# schametic.net
KiCad netlist of a schematic drawn in Altium Designer
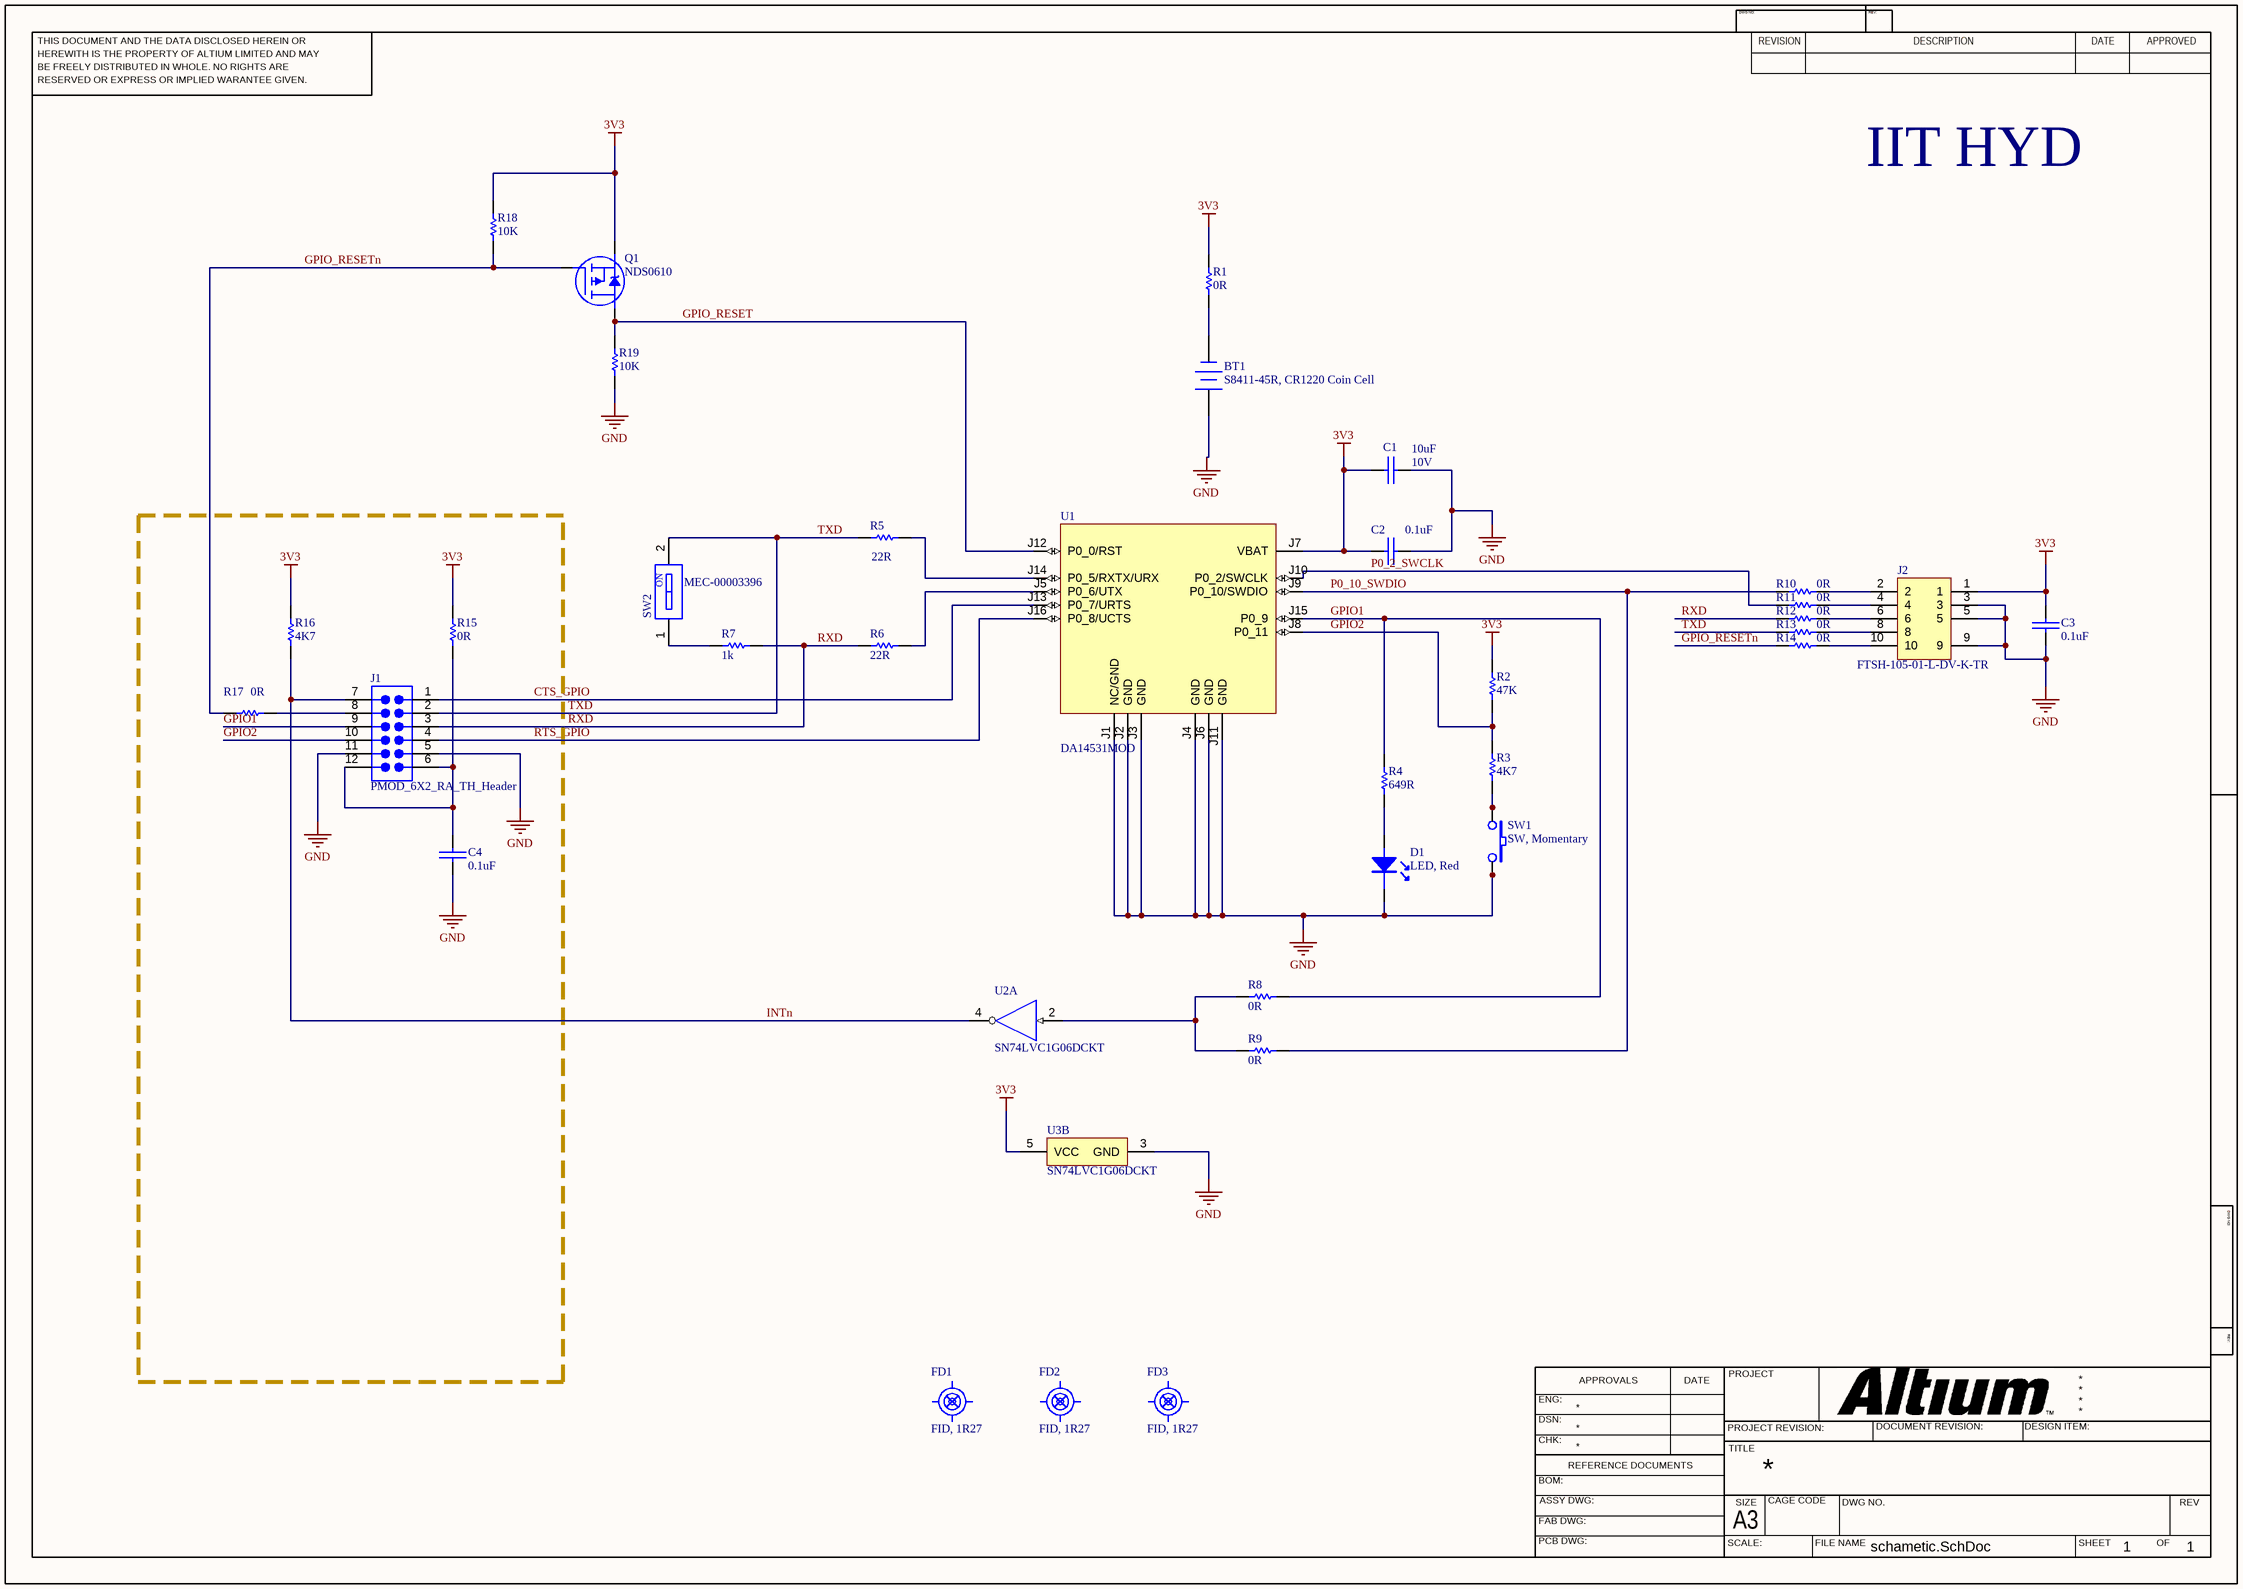
[diagram p0: schametic.SchDoc]

(export (version "E")
  (design (tool "Eeschema 10.0.6"))
  (components
    (comp (ref "BT1")
      (value "S8411-45R, CR1220 Coin Cell")
      (footprint "HWN_S8411-45R")
      (description "Battery Holder, 12 mm Coin Cell, CR1220 SM")
      (fields (field (name "MANUFACTURER'S PART #") "S8411-45R") (field (name "MANUFACTURER") "Harwin"))
      (libsource (lib "Low Power Bluetooth PMOD RevA") (part "BT-S8411-45R-SR-HWN"))
    )
    (comp (ref "C1")
      (value "10uF")
      (footprint "CAPC1608X10N")
      (description "Capacitor, 10uF, 10V, SM")
      (fields
        (field (name "MANUFACTURER'S PART #") "GRM188R61A106KE69D")
        (field (name "MANUFACTURER") "Murata")
        (field (name "VOLTAGE RATING") "10V")
      )
      (libsource (lib "Low Power Bluetooth PMOD RevA") (part "CI-10uF-10V-X5R-SR-MRT"))
    )
    (comp (ref "C2")
      (value "0.1uF")
      (footprint "CAPC1608X09N")
      (description "Capacitor, 0.1uF, 50V, SM")
      (fields
        (field (name "MANUFACTURER'S PART #") "CC0603KRX7R9BB104")
        (field (name "MANUFACTURER") "Yageo")
      )
      (libsource (lib "Low Power Bluetooth PMOD RevA") (part "CI-0.1uF-50V-X7R-SR-YAG"))
    )
    (comp (ref "C3")
      (value "0.1uF")
      (footprint "CAPC1608X09N")
      (description "Capacitor, 0.1uF, 50V, SM")
      (fields
        (field (name "MANUFACTURER'S PART #") "CC0603KRX7R9BB104")
        (field (name "MANUFACTURER") "Yageo")
      )
      (libsource (lib "Low Power Bluetooth PMOD RevA") (part "CI-0.1uF-50V-X7R-SR-YAG"))
    )
    (comp (ref "C4")
      (value "0.1uF")
      (footprint "CAPC1608X09N")
      (description "Capacitor, 0.1uF, 50V, SM")
      (fields
        (field (name "MANUFACTURER'S PART #") "CC0603KRX7R9BB104")
        (field (name "MANUFACTURER") "Yageo")
      )
      (libsource (lib "Low Power Bluetooth PMOD RevA") (part "CI-0.1uF-50V-X7R-SR-YAG"))
    )
    (comp (ref "D1")
      (value "LED, Red")
      (footprint "DIOC2012X08N_WTE")
      (description "LED, Red, 0805 SM")
      (fields
        (field (name "MANUFACTURER'S PART #") "150080RS75000")
        (field (name "MANUFACTURER") "Wurth Elektronik")
      )
      (libsource (lib "Low Power Bluetooth PMOD RevA") (part "DA-150080RS75000-SR-WTE"))
    )
    (comp (ref "FD1")
      (value "FID, 1R27")
      (footprint "FD_ML_1R27")
      (description "Fiducial, 1.27mm D, Multilayer")
      (fields (field (name "MANUFACTURER") "PCB Fabricator"))
      (libsource (lib "Low Power Bluetooth PMOD RevA") (part "FD-ML1R27-SR-BDH"))
    )
    (comp (ref "FD2")
      (value "FID, 1R27")
      (footprint "FD_ML_1R27")
      (description "Fiducial, 1.27mm D, Multilayer")
      (fields (field (name "MANUFACTURER") "PCB Fabricator"))
      (libsource (lib "Low Power Bluetooth PMOD RevA") (part "FD-ML1R27-SR-BDH"))
    )
    (comp (ref "FD3")
      (value "FID, 1R27")
      (footprint "FD_ML_1R27")
      (description "Fiducial, 1.27mm D, Multilayer")
      (fields (field (name "MANUFACTURER") "PCB Fabricator"))
      (libsource (lib "Low Power Bluetooth PMOD RevA") (part "FD-ML1R27-SR-BDH"))
    )
    (comp (ref "J1")
      (value "PMOD_6X2_RA_TH_Header")
      (footprint "PMOD-CONN2X6-RA-TH-HDR")
      (description "Male Header 0.1\" pitch PMOD 2x6 Right Angle, through hole")
      (libsource (lib "Low Power Bluetooth PMOD RevA") (part "CMP-024-000000-2"))
    )
    (comp (ref "J2")
      (value "FTSH-105-01-L-DV-K-TR")
      (footprint "SAM_FTSH-105-01-L-DV-007-K")
      (description "Connector, 2X5 Header, Vertical, 1.27mm Pitch, Pin 7, SM")
      (fields
        (field (name "MANUFACTURER'S PART #") "FTSH-105-01-L-DV-007-K")
        (field (name "MANUFACTURER") "Samtec")
      )
      (libsource (lib "Low Power Bluetooth PMOD RevA") (part "JH-2X5VH-FTSH-105-01-L-DV-007-K-SR-SAM"))
    )
    (comp (ref "Q1")
      (value "NDS0610")
      (footprint "SOT95P275X112-3NF")
      (description "Transistor, P-Ch Mosfet, 60V, 120mA, 10Ohm, SM")
      (fields (field (name "MANUFACTURER") "On Semiconductor"))
      (libsource (lib "Low Power Bluetooth PMOD RevA") (part "QA-NDS0610-SR-ONS"))
    )
    (comp (ref "R1")
      (value "0R")
      (footprint "RESC1608X06N")
      (description "Resistor, 0 ohms, 1/8W, 1%, SM")
      (fields (field (name "MANUFACTURER'S PART #") "RK73Z1JTTD") (field (name "MANUFACTURER") "KOA Speer"))
      (libsource (lib "Low Power Bluetooth PMOD RevA") (part "RP-0-SR-KOA"))
    )
    (comp (ref "R2")
      (value "47K")
      (footprint "RESC1608X06N")
      (description "Resistor, 47K ohms, 1/8W, 1%, SM")
      (fields
        (field (name "MANUFACTURER'S PART #") "RK73H1JTTD6802F")
        (field (name "MANUFACTURER") "KOA Speer")
      )
      (libsource (lib "Low Power Bluetooth PMOD RevA") (part "RP-47K-SR-KOA"))
    )
    (comp (ref "R3")
      (value "4K7")
      (footprint "RESC1608X06N")
      (description "Resistor, 4.7K ohms, 1/8W, 1%, SM")
      (fields
        (field (name "MANUFACTURER'S PART #") "RK73H1JTTD4701F")
        (field (name "MANUFACTURER") "KOA Speer")
      )
      (libsource (lib "Low Power Bluetooth PMOD RevA") (part "RP-4.7K-SR-KOA"))
    )
    (comp (ref "R4")
      (value "649R")
      (footprint "RESC1608X06N")
      (description "Resistor, 649 ohms, 1/8W, 1%, SM")
      (fields
        (field (name "MANUFACTURER'S PART #") "RK73H1JTTD6490F")
        (field (name "MANUFACTURER") "KOA Speer")
      )
      (libsource (lib "Low Power Bluetooth PMOD RevA") (part "RP-649-SR-KOA"))
    )
    (comp (ref "R5")
      (value "22R")
      (footprint "RESC1608X06N")
      (description "Resistor, 22 ohms, 1/8W, 1%, SM")
      (fields
        (field (name "MANUFACTURER'S PART #") "RK73H1JTTD22R0F")
        (field (name "MANUFACTURER") "KOA Speer")
      )
      (libsource (lib "Low Power Bluetooth PMOD RevA") (part "RP-22-SR-KOA"))
    )
    (comp (ref "R6")
      (value "22R")
      (footprint "RESC1608X06N")
      (description "Resistor, 22 ohms, 1/8W, 1%, SM")
      (fields
        (field (name "MANUFACTURER'S PART #") "RK73H1JTTD22R0F")
        (field (name "MANUFACTURER") "KOA Speer")
      )
      (libsource (lib "Low Power Bluetooth PMOD RevA") (part "RP-22-SR-KOA"))
    )
    (comp (ref "R7")
      (value "1k")
      (footprint "RESC0603-01")
      (description "Chip Resistor Thick Film 0603 1K0 ohm 1% 1/10W")
      (fields (field (name "TOLERANCE") "1%") (field (name "MFG") "Vishay Dale"))
      (libsource (lib "Low Power Bluetooth PMOD RevA") (part "CMP-009-00240-1"))
    )
    (comp (ref "R8")
      (value "0R")
      (footprint "RESC1608X06N")
      (description "Resistor, 0 ohms, 1/8W, 1%, SM")
      (fields (field (name "MANUFACTURER'S PART #") "RK73Z1JTTD") (field (name "MANUFACTURER") "KOA Speer"))
      (libsource (lib "Low Power Bluetooth PMOD RevA") (part "RP-0-SR-KOA"))
    )
    (comp (ref "R9")
      (value "0R")
      (footprint "RESC1608X06N")
      (description "Resistor, 0 ohms, 1/8W, 1%, SM")
      (fields (field (name "MANUFACTURER'S PART #") "RK73Z1JTTD") (field (name "MANUFACTURER") "KOA Speer"))
      (libsource (lib "Low Power Bluetooth PMOD RevA") (part "RP-0-SR-KOA"))
    )
    (comp (ref "R10")
      (value "0R")
      (footprint "RESC1608X06N")
      (description "Resistor, 0 ohms, 1/8W, 1%, SM")
      (fields (field (name "MANUFACTURER'S PART #") "RK73Z1JTTD") (field (name "MANUFACTURER") "KOA Speer"))
      (libsource (lib "Low Power Bluetooth PMOD RevA") (part "RP-0-SR-KOA"))
    )
    (comp (ref "R11")
      (value "0R")
      (footprint "RESC1608X06N")
      (description "Resistor, 0 ohms, 1/8W, 1%, SM")
      (fields (field (name "MANUFACTURER'S PART #") "RK73Z1JTTD") (field (name "MANUFACTURER") "KOA Speer"))
      (libsource (lib "Low Power Bluetooth PMOD RevA") (part "RP-0-SR-KOA"))
    )
    (comp (ref "R12")
      (value "0R")
      (footprint "RESC1608X06N")
      (description "Resistor, 0 ohms, 1/8W, 1%, SM")
      (fields (field (name "MANUFACTURER'S PART #") "RK73Z1JTTD") (field (name "MANUFACTURER") "KOA Speer"))
      (libsource (lib "Low Power Bluetooth PMOD RevA") (part "RP-0-SR-KOA"))
    )
    (comp (ref "R13")
      (value "0R")
      (footprint "RESC1608X06N")
      (description "Resistor, 0 ohms, 1/8W, 1%, SM")
      (fields (field (name "MANUFACTURER'S PART #") "RK73Z1JTTD") (field (name "MANUFACTURER") "KOA Speer"))
      (libsource (lib "Low Power Bluetooth PMOD RevA") (part "RP-0-SR-KOA"))
    )
    (comp (ref "R14")
      (value "0R")
      (footprint "RESC1608X06N")
      (description "Resistor, 0 ohms, 1/8W, 1%, SM")
      (fields (field (name "MANUFACTURER'S PART #") "RK73Z1JTTD") (field (name "MANUFACTURER") "KOA Speer"))
      (libsource (lib "Low Power Bluetooth PMOD RevA") (part "RP-0-SR-KOA"))
    )
    (comp (ref "R15")
      (value "0R")
      (footprint "RESC1608X06N")
      (description "Resistor, 0 ohms, 1/8W, 1%, SM")
      (fields (field (name "MANUFACTURER'S PART #") "RK73Z1JTTD") (field (name "MANUFACTURER") "KOA Speer"))
      (libsource (lib "Low Power Bluetooth PMOD RevA") (part "RP-0-SR-KOA"))
    )
    (comp (ref "R16")
      (value "4K7")
      (footprint "RESC1608X06N")
      (description "Resistor, 4.7K ohms, 1/8W, 1%, SM")
      (fields
        (field (name "MANUFACTURER'S PART #") "RK73H1JTTD4701F")
        (field (name "MANUFACTURER") "KOA Speer")
      )
      (libsource (lib "Low Power Bluetooth PMOD RevA") (part "RP-4.7K-SR-KOA"))
    )
    (comp (ref "R17")
      (value "0R")
      (footprint "RESC1608X06N")
      (description "Resistor, 0 ohms, 1/8W, 1%, SM")
      (fields (field (name "MANUFACTURER'S PART #") "RK73Z1JTTD") (field (name "MANUFACTURER") "KOA Speer"))
      (libsource (lib "Low Power Bluetooth PMOD RevA") (part "RP-0-SR-KOA"))
    )
    (comp (ref "R18")
      (value "10K")
      (footprint "RESC1608X06N")
      (description "Resistor, 10K ohms, 1/8W, 1%, SM")
      (fields
        (field (name "MANUFACTURER'S PART #") "RK73H1JTTD1002F")
        (field (name "MANUFACTURER") "KOA Speer")
      )
      (libsource (lib "Low Power Bluetooth PMOD RevA") (part "RP-10K-SR-KOA"))
    )
    (comp (ref "R19")
      (value "10K")
      (footprint "RESC1608X06N")
      (description "Resistor, 10K ohms, 1/8W, 1%, SM")
      (fields
        (field (name "MANUFACTURER'S PART #") "RK73H1JTTD1002F")
        (field (name "MANUFACTURER") "KOA Speer")
      )
      (libsource (lib "Low Power Bluetooth PMOD RevA") (part "RP-10K-SR-KOA"))
    )
    (comp (ref "SW1")
      (value "SW, Momentary")
      (footprint "SW_PTS810")
      (description "Switch, Pushbutton, Top Actuated, SM")
      (fields
        (field (name "MANUFACTURER'S PART #") "PTS810 SJG 250 SMTR LFS")
        (field (name "MANUFACTURER") "C&K Components")
      )
      (libsource (lib "Low Power Bluetooth PMOD RevA") (part "SW-PTS810SJG250-SR-CKC"))
    )
    (comp (ref "SW2")
      (value "MEC-00003396")
      (footprint "416131160801")
      (description "WS-DISV Small Compact SMT Flat Actuator with Top Tape 1.27 mm")
      (fields (field (name "VOLTAGE") "50V") (field (name "CHECKED") "OK"))
      (libsource (lib "Low Power Bluetooth PMOD RevA") (part "CMP-011-00036-1"))
    )
    (comp (ref "U1")
      (value "DA14531MOD")
      (footprint "DLG_DA14531MOD-00F01002")
      (description "DA14531MOD, Bluetooth Low Energy 5.1 Module, SM")
      (libsource (lib "Low Power Bluetooth PMOD RevA") (part "UD-DA14531MOD-00F01002-SR-DLG"))
    )
    (comp (ref "U2")
      (value "SN74LVC1G06DCKT")
      (footprint "SOT65P210X110-5N")
      (description "IC, Digital, Buffer,  Inverting, Open Drain, SM")
      (fields
        (field (name "MANUFACTURER") "Texas Instruments")
        (field (name "ALTERNATE PART #") "SN74LVC1G07DCKR")
      )
      (libsource (lib "") (part "UD-SN74LVC1G06DCKT-SR-TXI_1"))
    )
    (comp (ref "U3")
      (value "SN74LVC1G06DCKT")
      (footprint "SOT65P210X110-5N")
      (description "IC, Digital, Buffer,  Inverting, Open Drain, SM")
      (fields
        (field (name "MANUFACTURER") "Texas Instruments")
        (field (name "ALTERNATE PART #") "SN74LVC1G07DCKR")
      )
      (libsource (lib "Low Power Bluetooth PMOD RevA") (part "UD-SN74LVC1G06DCKT-SR-TXI"))
    )
  )
  (nets
    (net (code "1") (name "/CTS_GPIO") (class "Default")
      (node (ref "J1") (pin "1") (pinfunction "1_1") (pintype "passive"))
      (node (ref "U1") (pin "J13") (pinfunction "P0_7/URTS_J13") (pintype "bidirectional"))
    )
    (net (code "2") (name "/GPIO1") (class "Default")
      (node (ref "J1") (pin "9") (pinfunction "9_9") (pintype "passive"))
      (node (ref "R4") (pin "1") (pinfunction "1_1") (pintype "passive"))
      (node (ref "R8") (pin "2") (pinfunction "2_2") (pintype "passive"))
      (node (ref "U1") (pin "J15") (pinfunction "P0_9_J15") (pintype "bidirectional"))
    )
    (net (code "3") (name "/GPIO2") (class "Default")
      (node (ref "J1") (pin "10") (pinfunction "10_10") (pintype "passive"))
      (node (ref "R2") (pin "2") (pinfunction "2_2") (pintype "passive"))
      (node (ref "R3") (pin "1") (pinfunction "1_1") (pintype "passive"))
      (node (ref "U1") (pin "J8") (pinfunction "P0_11_J8") (pintype "bidirectional"))
    )
    (net (code "4") (name "/GPIO_RESET") (class "Default")
      (node (ref "Q1") (pin "D") (pinfunction "D_D") (pintype "passive"))
      (node (ref "R19") (pin "1") (pinfunction "1_1") (pintype "passive"))
      (node (ref "U1") (pin "J12") (pinfunction "P0_0/RST_J12") (pintype "bidirectional"))
    )
    (net (code "5") (name "/GPIO_RESETn") (class "Default")
      (node (ref "Q1") (pin "G") (pinfunction "G_G") (pintype "passive"))
      (node (ref "R14") (pin "1") (pinfunction "1_1") (pintype "passive"))
      (node (ref "R17") (pin "1") (pinfunction "1_1") (pintype "passive"))
      (node (ref "R18") (pin "2") (pinfunction "2_2") (pintype "passive"))
    )
    (net (code "6") (name "/INTn") (class "Default")
      (node (ref "J1") (pin "7") (pinfunction "7_7") (pintype "passive"))
      (node (ref "R16") (pin "2") (pinfunction "2_2") (pintype "passive"))
      (node (ref "U2") (pin "4") (pinfunction "Y_4") (pintype "tri_state"))
    )
    (net (code "7") (name "/P0_2_SWCLK") (class "Default")
      (node (ref "R11") (pin "1") (pinfunction "1_1") (pintype "passive"))
      (node (ref "U1") (pin "J10") (pinfunction "P0_2/SWCLK_J10") (pintype "bidirectional"))
    )
    (net (code "8") (name "/P0_10_SWDIO") (class "Default")
      (node (ref "R10") (pin "1") (pinfunction "1_1") (pintype "passive"))
      (node (ref "R9") (pin "2") (pinfunction "2_2") (pintype "passive"))
      (node (ref "U1") (pin "J9") (pinfunction "P0_10/SWDIO_J9") (pintype "bidirectional"))
    )
    (net (code "9") (name "/RTS_GPIO") (class "Default")
      (node (ref "J1") (pin "4") (pinfunction "4_4") (pintype "passive"))
      (node (ref "U1") (pin "J16") (pinfunction "P0_8/UCTS_J16") (pintype "bidirectional"))
    )
    (net (code "10") (name "/RXD") (class "Default")
      (node (ref "J1") (pin "3") (pinfunction "3_3") (pintype "passive"))
      (node (ref "R12") (pin "1") (pinfunction "1_1") (pintype "passive"))
      (node (ref "R6") (pin "1") (pinfunction "1_1") (pintype "passive"))
      (node (ref "R7") (pin "2") (pinfunction "2_2") (pintype "passive"))
    )
    (net (code "11") (name "/TXD") (class "Default")
      (node (ref "J1") (pin "2") (pinfunction "2_2") (pintype "passive"))
      (node (ref "R13") (pin "1") (pinfunction "1_1") (pintype "passive"))
      (node (ref "R5") (pin "1") (pinfunction "1_1") (pintype "passive"))
      (node (ref "SW2") (pin "2") (pinfunction "2_2") (pintype "passive"))
    )
    (net (code "12") (name "3V3") (class "Default")
      (node (ref "C1") (pin "1") (pinfunction "1_1") (pintype "passive"))
      (node (ref "C2") (pin "1") (pinfunction "1_1") (pintype "passive"))
      (node (ref "C3") (pin "1") (pinfunction "1_1") (pintype "passive"))
      (node (ref "J2") (pin "1") (pinfunction "1_1") (pintype "passive"))
      (node (ref "Q1") (pin "S") (pinfunction "S_S") (pintype "passive"))
      (node (ref "R1") (pin "1") (pinfunction "1_1") (pintype "passive"))
      (node (ref "R15") (pin "1") (pinfunction "1_1") (pintype "passive"))
      (node (ref "R16") (pin "1") (pinfunction "1_1") (pintype "passive"))
      (node (ref "R18") (pin "1") (pinfunction "1_1") (pintype "passive"))
      (node (ref "R2") (pin "1") (pinfunction "1_1") (pintype "passive"))
      (node (ref "U1") (pin "J7") (pinfunction "VBAT_J7") (pintype "power_in"))
      (node (ref "U3") (pin "5") (pinfunction "VCC_5") (pintype "power_in"))
    )
    (net (code "13") (name "GND") (class "Default")
      (node (ref "BT1") (pin "1") (pinfunction "+_1") (pintype "passive"))
      (node (ref "C1") (pin "2") (pinfunction "2_2") (pintype "passive"))
      (node (ref "C2") (pin "2") (pinfunction "2_2") (pintype "passive"))
      (node (ref "C3") (pin "2") (pinfunction "2_2") (pintype "passive"))
      (node (ref "C4") (pin "2") (pinfunction "2_2") (pintype "passive"))
      (node (ref "D1") (pin "K") (pintype "passive"))
      (node (ref "J1") (pin "11") (pinfunction "11_11") (pintype "passive"))
      (node (ref "J1") (pin "5") (pinfunction "5_5") (pintype "passive"))
      (node (ref "J2") (pin "3") (pinfunction "3_3") (pintype "passive"))
      (node (ref "J2") (pin "5") (pinfunction "5_5") (pintype "passive"))
      (node (ref "J2") (pin "9") (pinfunction "9_9") (pintype "passive"))
      (node (ref "R19") (pin "2") (pinfunction "2_2") (pintype "passive"))
      (node (ref "SW1") (pin "3") (pinfunction "3_3") (pintype "passive"))
      (node (ref "SW1") (pin "4") (pinfunction "4_4") (pintype "passive"))
      (node (ref "U1") (pin "J1") (pinfunction "NC/GND_J1") (pintype "power_in"))
      (node (ref "U1") (pin "J11") (pinfunction "GND_J11") (pintype "power_in"))
      (node (ref "U1") (pin "J2") (pinfunction "GND_J2") (pintype "power_in"))
      (node (ref "U1") (pin "J3") (pinfunction "GND_J3") (pintype "power_in"))
      (node (ref "U1") (pin "J4") (pinfunction "GND_J4") (pintype "power_in"))
      (node (ref "U1") (pin "J6") (pinfunction "GND_J6") (pintype "power_in"))
      (node (ref "U3") (pin "3") (pinfunction "GND_3") (pintype "power_in"))
    )
    (net (code "14") (name "Net-(BT1--)") (class "Default")
      (node (ref "BT1") (pin "2") (pinfunction "-_2") (pintype "passive"))
      (node (ref "R1") (pin "2") (pinfunction "2_2") (pintype "passive"))
    )
    (net (code "15") (name "Net-(C4-Pad1)") (class "Default")
      (node (ref "C4") (pin "1") (pinfunction "1_1") (pintype "passive"))
      (node (ref "J1") (pin "12") (pinfunction "12_12") (pintype "passive"))
      (node (ref "J1") (pin "6") (pinfunction "6_6") (pintype "passive"))
      (node (ref "R15") (pin "2") (pinfunction "2_2") (pintype "passive"))
    )
    (net (code "16") (name "Net-(D1-PadA)") (class "Default")
      (node (ref "D1") (pin "A") (pintype "passive"))
      (node (ref "R4") (pin "2") (pinfunction "2_2") (pintype "passive"))
    )
    (net (code "17") (name "Net-(J1-Pad8)") (class "Default")
      (node (ref "J1") (pin "8") (pinfunction "8_8") (pintype "passive"))
      (node (ref "R17") (pin "2") (pinfunction "2_2") (pintype "passive"))
    )
    (net (code "18") (name "Net-(J2-Pad2)") (class "Default")
      (node (ref "J2") (pin "2") (pinfunction "2_2") (pintype "passive"))
      (node (ref "R10") (pin "2") (pinfunction "2_2") (pintype "passive"))
    )
    (net (code "19") (name "Net-(J2-Pad4)") (class "Default")
      (node (ref "J2") (pin "4") (pinfunction "4_4") (pintype "passive"))
      (node (ref "R11") (pin "2") (pinfunction "2_2") (pintype "passive"))
    )
    (net (code "20") (name "Net-(J2-Pad6)") (class "Default")
      (node (ref "J2") (pin "6") (pinfunction "6_6") (pintype "passive"))
      (node (ref "R12") (pin "2") (pinfunction "2_2") (pintype "passive"))
    )
    (net (code "21") (name "Net-(J2-Pad8)") (class "Default")
      (node (ref "J2") (pin "8") (pinfunction "8_8") (pintype "passive"))
      (node (ref "R13") (pin "2") (pinfunction "2_2") (pintype "passive"))
    )
    (net (code "22") (name "Net-(J2-Pad10)") (class "Default")
      (node (ref "J2") (pin "10") (pinfunction "10_10") (pintype "passive"))
      (node (ref "R14") (pin "2") (pinfunction "2_2") (pintype "passive"))
    )
    (net (code "23") (name "Net-(R3-Pad2)") (class "Default")
      (node (ref "R3") (pin "2") (pinfunction "2_2") (pintype "passive"))
      (node (ref "SW1") (pin "1") (pinfunction "1_1") (pintype "passive"))
      (node (ref "SW1") (pin "2") (pinfunction "2_2") (pintype "passive"))
    )
    (net (code "24") (name "Net-(R7-Pad1)") (class "Default")
      (node (ref "R7") (pin "1") (pinfunction "1_1") (pintype "passive"))
      (node (ref "SW2") (pin "1") (pinfunction "1_1") (pintype "passive"))
    )
    (net (code "25") (name "Net-(U1-P0_5{slash}RXTX{slash}URX)") (class "Default")
      (node (ref "R5") (pin "2") (pinfunction "2_2") (pintype "passive"))
      (node (ref "U1") (pin "J14") (pinfunction "P0_5/RXTX/URX_J14") (pintype "bidirectional"))
    )
    (net (code "26") (name "Net-(U1-P0_6{slash}UTX)") (class "Default")
      (node (ref "R6") (pin "2") (pinfunction "2_2") (pintype "passive"))
      (node (ref "U1") (pin "J5") (pinfunction "P0_6/UTX_J5") (pintype "bidirectional"))
    )
    (net (code "27") (name "Net-(U2A-A)") (class "Default")
      (node (ref "R8") (pin "1") (pinfunction "1_1") (pintype "passive"))
      (node (ref "R9") (pin "1") (pinfunction "1_1") (pintype "passive"))
      (node (ref "U2") (pin "2") (pinfunction "A_2") (pintype "input"))
    )
  )
)
